# SCH_Modules.net
KiCad netlist of a schematic drawn in Altium Designer
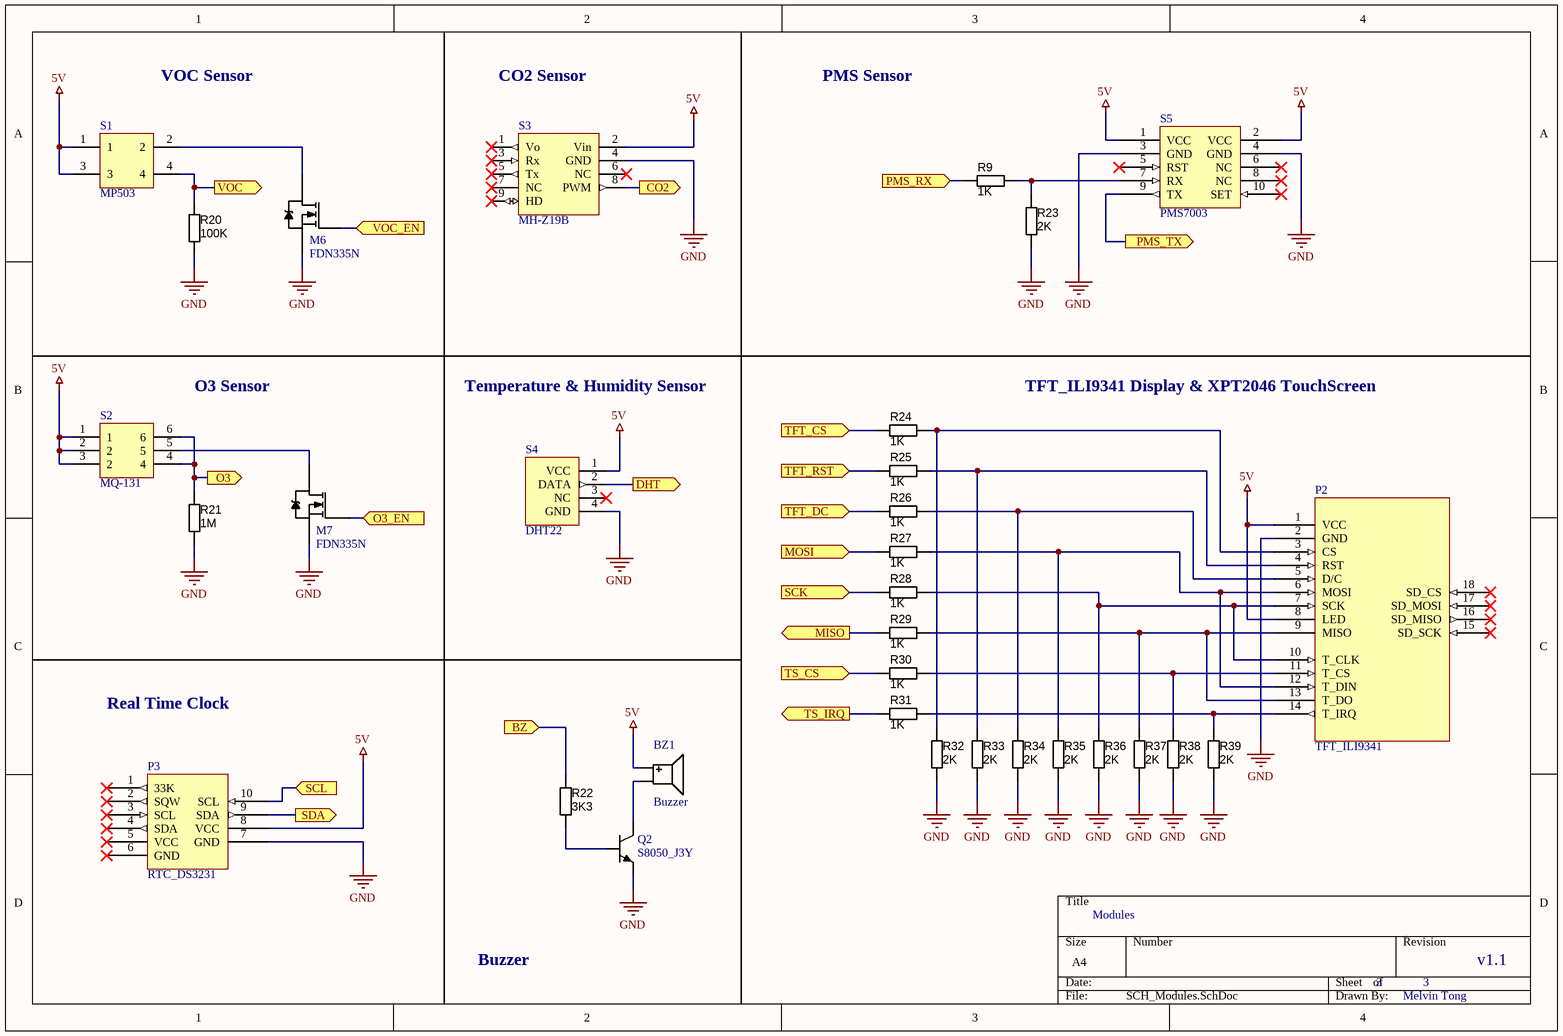
[diagram p0: SCH_Modules.SchDoc]

(export (version "E")
  (design (tool "Eeschema 10.0.6"))
  (components
    (comp (ref "BZ1")
      (value "Buzzer")
      (footprint "BZ_12085")
      (description "Buzzer passive 5 VAC")
      (libsource (lib "SchLib_AirMeter") (part "Buzzer"))
    )
    (comp (ref "M6")
      (value "FDN335N")
      (footprint "SOT23_213")
      (libsource (lib "SchLib_AirMeter") (part "NMOS"))
    )
    (comp (ref "M7")
      (value "FDN335N")
      (footprint "SOT23_213")
      (libsource (lib "SchLib_AirMeter") (part "NMOS"))
    )
    (comp (ref "P2")
      (value "TFT_ILI9341")
      (footprint "TFT_ILI9341")
      (libsource (lib "SchLib_AirMeter") (part "TFT_ILI9341"))
    )
    (comp (ref "P3")
      (value "RTC_DS3231")
      (footprint "DS3231 RTC")
      (description "Real Time Clock")
      (libsource (lib "SchLib_AirMeter") (part "RTC_DS3231"))
    )
    (comp (ref "Q2")
      (value "S8050_J3Y")
      (footprint "SOT23_213")
      (libsource (lib "SchLib_AirMeter") (part "NPN"))
    )
    (comp (ref "R9")
      (value "1K")
      (footprint "RESC3216X70N")
      (description "Resistor SMD, 1206")
      (libsource (lib "SchLib_AirMeter") (part "RES_1K"))
    )
    (comp (ref "R20")
      (value "100K")
      (footprint "RESC3216X70N")
      (description "Resistor SMD, 1206")
      (libsource (lib "SchLib_AirMeter") (part "RES_100K"))
    )
    (comp (ref "R21")
      (value "1M")
      (footprint "RESC3216X70N")
      (description "Resistor SMD, 1206")
      (libsource (lib "SchLib_AirMeter") (part "RES_1M"))
    )
    (comp (ref "R22")
      (value "3K3")
      (footprint "RESC3216X70N")
      (description "Resistor SMD, 1206")
      (libsource (lib "SchLib_AirMeter") (part "RES_3K3"))
    )
    (comp (ref "R23")
      (value "2K")
      (footprint "RESC3216X70N")
      (description "Resistor SMD, 1206")
      (libsource (lib "SchLib_AirMeter") (part "RES_2K"))
    )
    (comp (ref "R24")
      (value "1K")
      (footprint "RESC3216X70N")
      (description "Resistor SMD, 1206")
      (libsource (lib "SchLib_AirMeter") (part "RES_1K"))
    )
    (comp (ref "R25")
      (value "1K")
      (footprint "RESC3216X70N")
      (description "Resistor SMD, 1206")
      (libsource (lib "SchLib_AirMeter") (part "RES_1K"))
    )
    (comp (ref "R26")
      (value "1K")
      (footprint "RESC3216X70N")
      (description "Resistor SMD, 1206")
      (libsource (lib "SchLib_AirMeter") (part "RES_1K"))
    )
    (comp (ref "R27")
      (value "1K")
      (footprint "RESC3216X70N")
      (description "Resistor SMD, 1206")
      (libsource (lib "SchLib_AirMeter") (part "RES_1K"))
    )
    (comp (ref "R28")
      (value "1K")
      (footprint "RESC3216X70N")
      (description "Resistor SMD, 1206")
      (libsource (lib "SchLib_AirMeter") (part "RES_1K"))
    )
    (comp (ref "R29")
      (value "1K")
      (footprint "RESC3216X70N")
      (description "Resistor SMD, 1206")
      (libsource (lib "SchLib_AirMeter") (part "RES_1K"))
    )
    (comp (ref "R30")
      (value "1K")
      (footprint "RESC3216X70N")
      (description "Resistor SMD, 1206")
      (libsource (lib "SchLib_AirMeter") (part "RES_1K"))
    )
    (comp (ref "R31")
      (value "1K")
      (footprint "RESC3216X70N")
      (description "Resistor SMD, 1206")
      (libsource (lib "SchLib_AirMeter") (part "RES_1K"))
    )
    (comp (ref "R32")
      (value "2K")
      (footprint "RESC3216X70N")
      (description "Resistor SMD, 1206")
      (libsource (lib "SchLib_AirMeter") (part "RES_2K"))
    )
    (comp (ref "R33")
      (value "2K")
      (footprint "RESC3216X70N")
      (description "Resistor SMD, 1206")
      (libsource (lib "SchLib_AirMeter") (part "RES_2K"))
    )
    (comp (ref "R34")
      (value "2K")
      (footprint "RESC3216X70N")
      (description "Resistor SMD, 1206")
      (libsource (lib "SchLib_AirMeter") (part "RES_2K"))
    )
    (comp (ref "R35")
      (value "2K")
      (footprint "RESC3216X70N")
      (description "Resistor SMD, 1206")
      (libsource (lib "SchLib_AirMeter") (part "RES_2K"))
    )
    (comp (ref "R36")
      (value "2K")
      (footprint "RESC3216X70N")
      (description "Resistor SMD, 1206")
      (libsource (lib "SchLib_AirMeter") (part "RES_2K"))
    )
    (comp (ref "R37")
      (value "2K")
      (footprint "RESC3216X70N")
      (description "Resistor SMD, 1206")
      (libsource (lib "SchLib_AirMeter") (part "RES_2K"))
    )
    (comp (ref "R38")
      (value "2K")
      (footprint "RESC3216X70N")
      (description "Resistor SMD, 1206")
      (libsource (lib "SchLib_AirMeter") (part "RES_2K"))
    )
    (comp (ref "R39")
      (value "2K")
      (footprint "RESC3216X70N")
      (description "Resistor SMD, 1206")
      (libsource (lib "SchLib_AirMeter") (part "RES_2K"))
    )
    (comp (ref "S1")
      (value "MP503")
      (footprint "MP503 VOC Sensor")
      (description "VOC Sensor")
      (libsource (lib "SchLib_AirMeter") (part "MP503"))
    )
    (comp (ref "S2")
      (value "MQ-131")
      (footprint "MQ-131 Ozone Sensor")
      (description "Ozone Sensor")
      (libsource (lib "SchLib_AirMeter") (part "MQ-131"))
    )
    (comp (ref "S3")
      (value "MH-Z19B")
      (footprint "MH-Z19B CO2 Sensor")
      (description "CO2 Sensor")
      (libsource (lib "SchLib_AirMeter") (part "MH-Z19B"))
    )
    (comp (ref "S4") (value "DHT22") (footprint "DHT22") (libsource (lib "SchLib_AirMeter") (part "DHT22")))
    (comp (ref "S5")
      (value "PMS7003")
      (footprint "PMS7003")
      (description "Particle air sensor. 1um, 2.5um, 10um")
      (libsource (lib "SchLib_AirMeter") (part "PMS7003"))
    )
  )
  (nets
    (net (code "1") (name "/BZ") (class "Default")
      (node (ref "R22") (pin "1") (pinfunction "1_1") (pintype "passive"))
    )
    (net (code "2") (name "/CO2") (class "Default")
      (node (ref "S3") (pin "8") (pinfunction "PWM_8") (pintype "output"))
    )
    (net (code "3") (name "/DHT") (class "Default")
      (node (ref "S4") (pin "2") (pinfunction "DATA_2") (pintype "output"))
    )
    (net (code "4") (name "/MISO") (class "Default")
      (node (ref "R29") (pin "1") (pinfunction "1_1") (pintype "passive"))
    )
    (net (code "5") (name "/MOSI") (class "Default")
      (node (ref "R27") (pin "1") (pinfunction "1_1") (pintype "passive"))
    )
    (net (code "6") (name "/O3") (class "Default")
      (node (ref "R21") (pin "1") (pinfunction "1_1") (pintype "passive"))
      (node (ref "S2") (pin "4") (pinfunction "4_4") (pintype "passive"))
      (node (ref "S2") (pin "6") (pinfunction "6_6") (pintype "passive"))
    )
    (net (code "7") (name "/O3_EN") (class "Default")
      (node (ref "M7") (pin "1") (pinfunction "G_1") (pintype "passive"))
    )
    (net (code "8") (name "/PMS_RX") (class "Default")
      (node (ref "R9") (pin "1") (pinfunction "1_1") (pintype "passive"))
    )
    (net (code "9") (name "/PMS_TX") (class "Default")
      (node (ref "S5") (pin "9") (pinfunction "TX_9") (pintype "output"))
    )
    (net (code "10") (name "/SCK") (class "Default")
      (node (ref "R28") (pin "1") (pinfunction "1_1") (pintype "passive"))
    )
    (net (code "11") (name "/SCL") (class "Default")
      (node (ref "P3") (pin "10") (pinfunction "SCL_10") (pintype "input"))
    )
    (net (code "12") (name "/SDA") (class "Default")
      (node (ref "P3") (pin "9") (pinfunction "SDA_9") (pintype "output"))
    )
    (net (code "13") (name "/TFT_CS") (class "Default")
      (node (ref "R24") (pin "1") (pinfunction "1_1") (pintype "passive"))
    )
    (net (code "14") (name "/TFT_DC") (class "Default")
      (node (ref "R26") (pin "1") (pinfunction "1_1") (pintype "passive"))
    )
    (net (code "15") (name "/TFT_RST") (class "Default")
      (node (ref "R25") (pin "1") (pinfunction "1_1") (pintype "passive"))
    )
    (net (code "16") (name "/TS_CS") (class "Default")
      (node (ref "R30") (pin "1") (pinfunction "1_1") (pintype "passive"))
    )
    (net (code "17") (name "/TS_IRQ") (class "Default")
      (node (ref "R31") (pin "1") (pinfunction "1_1") (pintype "passive"))
    )
    (net (code "18") (name "/VOC") (class "Default")
      (node (ref "R20") (pin "1") (pinfunction "1_1") (pintype "passive"))
      (node (ref "S1") (pin "4") (pinfunction "4_4") (pintype "passive"))
    )
    (net (code "19") (name "/VOC_EN") (class "Default")
      (node (ref "M6") (pin "1") (pinfunction "G_1") (pintype "passive"))
    )
    (net (code "20") (name "5V") (class "Default")
      (node (ref "BZ1") (pin "1") (pinfunction "Positive_1") (pintype "passive"))
      (node (ref "P2") (pin "1") (pinfunction "VCC_1") (pintype "power_in"))
      (node (ref "P2") (pin "8") (pinfunction "LED_8") (pintype "power_in"))
      (node (ref "P3") (pin "8") (pinfunction "VCC_8") (pintype "power_in"))
      (node (ref "S1") (pin "1") (pinfunction "1_1") (pintype "passive"))
      (node (ref "S1") (pin "3") (pinfunction "3_3") (pintype "passive"))
      (node (ref "S2") (pin "1") (pinfunction "1_1") (pintype "passive"))
      (node (ref "S2") (pin "2") (pinfunction "2_2") (pintype "passive"))
      (node (ref "S2") (pin "3") (pinfunction "2_3") (pintype "passive"))
      (node (ref "S3") (pin "2") (pinfunction "Vin_2") (pintype "power_in"))
      (node (ref "S4") (pin "1") (pinfunction "VCC_1") (pintype "power_in"))
      (node (ref "S5") (pin "1") (pinfunction "VCC_1") (pintype "power_in"))
      (node (ref "S5") (pin "2") (pinfunction "VCC_2") (pintype "power_in"))
    )
    (net (code "21") (name "GND") (class "Default")
      (node (ref "M6") (pin "2") (pinfunction "S_2") (pintype "passive"))
      (node (ref "M7") (pin "2") (pinfunction "S_2") (pintype "passive"))
      (node (ref "P2") (pin "2") (pinfunction "GND_2") (pintype "power_in"))
      (node (ref "P3") (pin "7") (pinfunction "GND_7") (pintype "power_in"))
      (node (ref "Q2") (pin "2") (pinfunction "E_2") (pintype "passive"))
      (node (ref "R20") (pin "2") (pinfunction "2_2") (pintype "passive"))
      (node (ref "R21") (pin "2") (pinfunction "2_2") (pintype "passive"))
      (node (ref "R23") (pin "2") (pinfunction "2_2") (pintype "passive"))
      (node (ref "R32") (pin "2") (pinfunction "2_2") (pintype "passive"))
      (node (ref "R33") (pin "2") (pinfunction "2_2") (pintype "passive"))
      (node (ref "R34") (pin "2") (pinfunction "2_2") (pintype "passive"))
      (node (ref "R35") (pin "2") (pinfunction "2_2") (pintype "passive"))
      (node (ref "R36") (pin "2") (pinfunction "2_2") (pintype "passive"))
      (node (ref "R37") (pin "2") (pinfunction "2_2") (pintype "passive"))
      (node (ref "R38") (pin "2") (pinfunction "2_2") (pintype "passive"))
      (node (ref "R39") (pin "2") (pinfunction "2_2") (pintype "passive"))
      (node (ref "S3") (pin "4") (pinfunction "GND_4") (pintype "power_in"))
      (node (ref "S4") (pin "4") (pinfunction "GND_4") (pintype "power_in"))
      (node (ref "S5") (pin "3") (pinfunction "GND_3") (pintype "power_in"))
      (node (ref "S5") (pin "4") (pinfunction "GND_4") (pintype "power_in"))
    )
    (net (code "22") (name "Net-(BZ1-Negative)") (class "Default")
      (node (ref "BZ1") (pin "2") (pinfunction "Negative_2") (pintype "passive"))
      (node (ref "Q2") (pin "3") (pinfunction "C_3") (pintype "passive"))
    )
    (net (code "23") (name "Net-(M6-D)") (class "Default")
      (node (ref "M6") (pin "3") (pinfunction "D_3") (pintype "passive"))
      (node (ref "S1") (pin "2") (pinfunction "2_2") (pintype "passive"))
    )
    (net (code "24") (name "Net-(M7-D)") (class "Default")
      (node (ref "M7") (pin "3") (pinfunction "D_3") (pintype "passive"))
      (node (ref "S2") (pin "5") (pinfunction "5_5") (pintype "passive"))
    )
    (net (code "25") (name "Net-(P2-CS)") (class "Default")
      (node (ref "P2") (pin "3") (pinfunction "CS_3") (pintype "input"))
      (node (ref "R24") (pin "2") (pinfunction "2_2") (pintype "passive"))
      (node (ref "R32") (pin "1") (pinfunction "1_1") (pintype "passive"))
    )
    (net (code "26") (name "Net-(P2-D{slash}C)") (class "Default")
      (node (ref "P2") (pin "5") (pinfunction "D/C_5") (pintype "input"))
      (node (ref "R26") (pin "2") (pinfunction "2_2") (pintype "passive"))
      (node (ref "R34") (pin "1") (pinfunction "1_1") (pintype "passive"))
    )
    (net (code "27") (name "Net-(P2-MISO)") (class "Default")
      (node (ref "P2") (pin "13") (pinfunction "T_DO_13") (pintype "passive"))
      (node (ref "P2") (pin "9") (pinfunction "MISO_9") (pintype "passive"))
      (node (ref "R29") (pin "2") (pinfunction "2_2") (pintype "passive"))
      (node (ref "R37") (pin "1") (pinfunction "1_1") (pintype "passive"))
    )
    (net (code "28") (name "Net-(P2-MOSI)") (class "Default")
      (node (ref "P2") (pin "12") (pinfunction "T_DIN_12") (pintype "input"))
      (node (ref "P2") (pin "6") (pinfunction "MOSI_6") (pintype "input"))
      (node (ref "R27") (pin "2") (pinfunction "2_2") (pintype "passive"))
      (node (ref "R35") (pin "1") (pinfunction "1_1") (pintype "passive"))
    )
    (net (code "29") (name "Net-(P2-RST)") (class "Default")
      (node (ref "P2") (pin "4") (pinfunction "RST_4") (pintype "input"))
      (node (ref "R25") (pin "2") (pinfunction "2_2") (pintype "passive"))
      (node (ref "R33") (pin "1") (pinfunction "1_1") (pintype "passive"))
    )
    (net (code "30") (name "Net-(P2-SCK)") (class "Default")
      (node (ref "P2") (pin "10") (pinfunction "T_CLK_10") (pintype "input"))
      (node (ref "P2") (pin "7") (pinfunction "SCK_7") (pintype "input"))
      (node (ref "R28") (pin "2") (pinfunction "2_2") (pintype "passive"))
      (node (ref "R36") (pin "1") (pinfunction "1_1") (pintype "passive"))
    )
    (net (code "31") (name "Net-(P2-T_CS)") (class "Default")
      (node (ref "P2") (pin "11") (pinfunction "T_CS_11") (pintype "input"))
      (node (ref "R30") (pin "2") (pinfunction "2_2") (pintype "passive"))
      (node (ref "R38") (pin "1") (pinfunction "1_1") (pintype "passive"))
    )
    (net (code "32") (name "Net-(P2-T_IRQ)") (class "Default")
      (node (ref "P2") (pin "14") (pinfunction "T_IRQ_14") (pintype "output"))
      (node (ref "R31") (pin "2") (pinfunction "2_2") (pintype "passive"))
      (node (ref "R39") (pin "1") (pinfunction "1_1") (pintype "passive"))
    )
    (net (code "33") (name "Net-(Q2-B)") (class "Default")
      (node (ref "Q2") (pin "1") (pinfunction "B_1") (pintype "passive"))
      (node (ref "R22") (pin "2") (pinfunction "2_2") (pintype "passive"))
    )
    (net (code "34") (name "Net-(S5-RX)") (class "Default")
      (node (ref "R23") (pin "1") (pinfunction "1_1") (pintype "passive"))
      (node (ref "R9") (pin "2") (pinfunction "2_2") (pintype "passive"))
      (node (ref "S5") (pin "7") (pinfunction "RX_7") (pintype "input"))
    )
    (net (code "35") (name "unconnected-(P2-SD_CS-Pad18)") (class "Default")
      (node (ref "P2") (pin "18") (pinfunction "SD_CS_18") (pintype "input+no_connect"))
    )
    (net (code "36") (name "unconnected-(P2-SD_MISO-Pad16)") (class "Default")
      (node (ref "P2") (pin "16") (pinfunction "SD_MISO_16") (pintype "output+no_connect"))
    )
    (net (code "37") (name "unconnected-(P2-SD_MOSI-Pad17)") (class "Default")
      (node (ref "P2") (pin "17") (pinfunction "SD_MOSI_17") (pintype "input+no_connect"))
    )
    (net (code "38") (name "unconnected-(P2-SD_SCK-Pad15)") (class "Default")
      (node (ref "P2") (pin "15") (pinfunction "SD_SCK_15") (pintype "input+no_connect"))
    )
    (net (code "39") (name "unconnected-(P3-33K-Pad1)") (class "Default")
      (node (ref "P3") (pin "1") (pinfunction "33K_1") (pintype "output+no_connect"))
    )
    (net (code "40") (name "unconnected-(P3-GND-Pad6)") (class "Default")
      (node (ref "P3") (pin "6") (pinfunction "GND_6") (pintype "power_in+no_connect"))
    )
    (net (code "41") (name "unconnected-(P3-SCL-Pad3)") (class "Default")
      (node (ref "P3") (pin "3") (pinfunction "SCL_3") (pintype "input+no_connect"))
    )
    (net (code "42") (name "unconnected-(P3-SDA-Pad4)") (class "Default")
      (node (ref "P3") (pin "4") (pinfunction "SDA_4") (pintype "output+no_connect"))
    )
    (net (code "43") (name "unconnected-(P3-SQW-Pad2)") (class "Default")
      (node (ref "P3") (pin "2") (pinfunction "SQW_2") (pintype "output+no_connect"))
    )
    (net (code "44") (name "unconnected-(P3-VCC-Pad5)") (class "Default")
      (node (ref "P3") (pin "5") (pinfunction "VCC_5") (pintype "power_in+no_connect"))
    )
    (net (code "45") (name "unconnected-(S3-HD-Pad9)") (class "Default")
      (node (ref "S3") (pin "9") (pinfunction "HD_9") (pintype "bidirectional+no_connect"))
    )
    (net (code "46") (name "unconnected-(S3-NC-Pad6)") (class "Default")
      (node (ref "S3") (pin "6") (pinfunction "NC_6") (pintype "passive+no_connect"))
    )
    (net (code "47") (name "unconnected-(S3-NC-Pad7)") (class "Default")
      (node (ref "S3") (pin "7") (pinfunction "NC_7") (pintype "passive+no_connect"))
    )
    (net (code "48") (name "unconnected-(S3-Rx-Pad3)") (class "Default")
      (node (ref "S3") (pin "3") (pinfunction "Rx_3") (pintype "input+no_connect"))
    )
    (net (code "49") (name "unconnected-(S3-Tx-Pad5)") (class "Default")
      (node (ref "S3") (pin "5") (pinfunction "Tx_5") (pintype "output+no_connect"))
    )
    (net (code "50") (name "unconnected-(S3-Vo-Pad1)") (class "Default")
      (node (ref "S3") (pin "1") (pinfunction "Vo_1") (pintype "output+no_connect"))
    )
    (net (code "51") (name "unconnected-(S4-NC-Pad3)") (class "Default")
      (node (ref "S4") (pin "3") (pinfunction "NC_3") (pintype "power_in+no_connect"))
    )
    (net (code "52") (name "unconnected-(S5-NC-Pad6)") (class "Default")
      (node (ref "S5") (pin "6") (pinfunction "NC_6") (pintype "passive+no_connect"))
    )
    (net (code "53") (name "unconnected-(S5-NC-Pad8)") (class "Default")
      (node (ref "S5") (pin "8") (pinfunction "NC_8") (pintype "passive+no_connect"))
    )
    (net (code "54") (name "unconnected-(S5-RST-Pad5)") (class "Default")
      (node (ref "S5") (pin "5") (pinfunction "RST_5") (pintype "input+no_connect"))
    )
    (net (code "55") (name "unconnected-(S5-SET-Pad10)") (class "Default")
      (node (ref "S5") (pin "10") (pinfunction "SET_10") (pintype "input+no_connect"))
    )
  )
)
